# EEPROM-smt.net
KiCad netlist of a schematic drawn in EAGLE
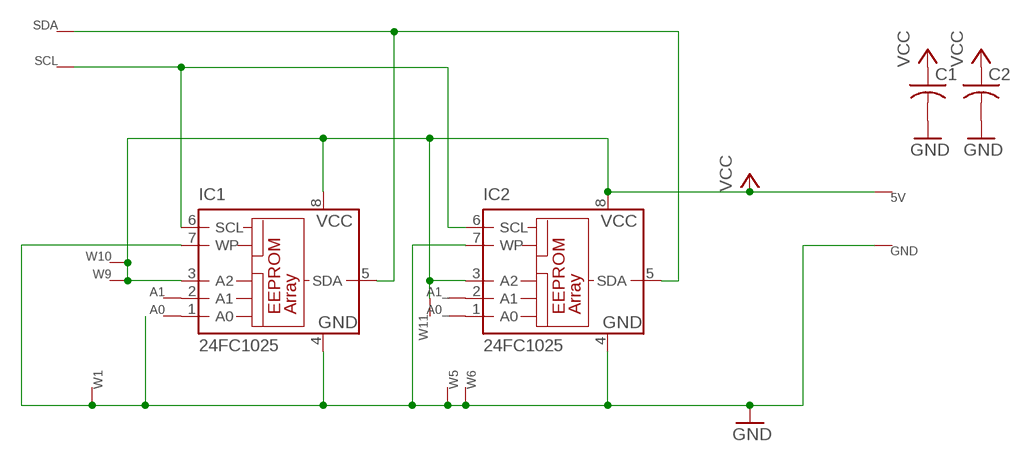
[diagram p0: schematic, sheet 1]

(export (version "E")
  (design (tool "Eeschema 10.0.6"))
  (components
    (comp (ref "5V")
      (value "WIRE-VIA8")
      (footprint "eagle-import:VIA8")
      (libsource (lib "eagle-import") (part "WIRE-VIA8"))
    )
    (comp (ref "A0")
      (value "WIRE-R6")
      (footprint "eagle-import:VIA6")
      (libsource (lib "eagle-import") (part "WIRE-R6"))
    )
    (comp (ref "A0_")
      (value "WIRE-R6")
      (footprint "eagle-import:VIA6")
      (libsource (lib "eagle-import") (part "WIRE-R6"))
    )
    (comp (ref "A1")
      (value "WIRE-R6")
      (footprint "eagle-import:VIA6")
      (libsource (lib "eagle-import") (part "WIRE-R6"))
    )
    (comp (ref "A1_")
      (value "WIRE-R6")
      (footprint "eagle-import:VIA6")
      (libsource (lib "eagle-import") (part "WIRE-R6"))
    )
    (comp (ref "C1")
      (value "C-USC0805")
      (footprint "eagle-import:C0805")
      (libsource (lib "eagle-import") (part "C-USC0805"))
    )
    (comp (ref "C2")
      (value "C-USC0805")
      (footprint "eagle-import:C0805")
      (libsource (lib "eagle-import") (part "C-USC0805"))
    )
    (comp (ref "GND")
      (value "WIRE-VIA8")
      (footprint "eagle-import:VIA8")
      (libsource (lib "eagle-import") (part "WIRE-VIA8"))
    )
    (comp (ref "IC1")
      (value "24FC1025")
      (footprint "eagle-import:SO-08")
      (fields (field (name "MF") "MICROCHIP") (field (name "MPN") "24LC128-I/SNG"))
      (libsource (lib "eagle-import") (part "24SNLC128"))
    )
    (comp (ref "IC2")
      (value "24FC1025")
      (footprint "eagle-import:SO-08")
      (fields (field (name "MF") "MICROCHIP") (field (name "MPN") "24LC128-I/SNG"))
      (libsource (lib "eagle-import") (part "24SNLC128"))
    )
    (comp (ref "SCL")
      (value "WIRE-VIA8")
      (footprint "eagle-import:VIA8")
      (libsource (lib "eagle-import") (part "WIRE-VIA8"))
    )
    (comp (ref "SDA")
      (value "WIRE-VIA8")
      (footprint "eagle-import:VIA8")
      (libsource (lib "eagle-import") (part "WIRE-VIA8"))
    )
    (comp (ref "W1")
      (value "WIRE-VIA8")
      (footprint "eagle-import:VIA8")
      (libsource (lib "eagle-import") (part "WIRE-VIA8"))
    )
    (comp (ref "W5")
      (value "WIRE-VIA8")
      (footprint "eagle-import:VIA8")
      (libsource (lib "eagle-import") (part "WIRE-VIA8"))
    )
    (comp (ref "W6")
      (value "WIRE-VIA8")
      (footprint "eagle-import:VIA8")
      (libsource (lib "eagle-import") (part "WIRE-VIA8"))
    )
    (comp (ref "W9")
      (value "WIRE-VIA8")
      (footprint "eagle-import:VIA8")
      (libsource (lib "eagle-import") (part "WIRE-VIA8"))
    )
    (comp (ref "W10")
      (value "WIRE-VIA8")
      (footprint "eagle-import:VIA8")
      (libsource (lib "eagle-import") (part "WIRE-VIA8"))
    )
    (comp (ref "W11")
      (value "WIRE-VIA8")
      (footprint "eagle-import:VIA8")
      (libsource (lib "eagle-import") (part "WIRE-VIA8"))
    )
  )
  (nets
    (net (code "1") (name "GND") (class "Default")
      (node (ref "C1") (pin "2") (pinfunction "2_2") (pintype "passive"))
      (node (ref "C2") (pin "2") (pinfunction "2_2") (pintype "passive"))
      (node (ref "GND") (pin "P$1") (pinfunction "P$1_P$1") (pintype "bidirectional"))
      (node (ref "IC1") (pin "4") (pinfunction "GND_4") (pintype "power_in"))
      (node (ref "IC1") (pin "7") (pinfunction "WP_7") (pintype "input"))
      (node (ref "IC2") (pin "4") (pinfunction "GND_4") (pintype "power_in"))
      (node (ref "IC2") (pin "7") (pinfunction "WP_7") (pintype "input"))
      (node (ref "W1") (pin "P$1") (pinfunction "P$1_P$1") (pintype "bidirectional"))
      (node (ref "W5") (pin "P$1") (pinfunction "P$1_P$1") (pintype "bidirectional"))
      (node (ref "W6") (pin "P$1") (pinfunction "P$1_P$1") (pintype "bidirectional"))
    )
    (net (code "2") (name "Net-(IC1-A0)") (class "Default")
      (node (ref "A0") (pin "P$1") (pinfunction "P$1_P$1") (pintype "bidirectional"))
      (node (ref "IC1") (pin "1") (pinfunction "A0_1") (pintype "input"))
    )
    (net (code "3") (name "Net-(IC1-A1)") (class "Default")
      (node (ref "A1") (pin "P$1") (pinfunction "P$1_P$1") (pintype "bidirectional"))
      (node (ref "IC1") (pin "2") (pinfunction "A1_2") (pintype "input"))
    )
    (net (code "4") (name "Net-(IC1-SCL)") (class "Default")
      (node (ref "IC1") (pin "6") (pinfunction "SCL_6") (pintype "input"))
      (node (ref "IC2") (pin "6") (pinfunction "SCL_6") (pintype "input"))
      (node (ref "SCL") (pin "P$1") (pinfunction "P$1_P$1") (pintype "bidirectional"))
    )
    (net (code "5") (name "Net-(IC1-SDA)") (class "Default")
      (node (ref "IC1") (pin "5") (pinfunction "SDA_5") (pintype "bidirectional"))
      (node (ref "IC2") (pin "5") (pinfunction "SDA_5") (pintype "bidirectional"))
      (node (ref "SDA") (pin "P$1") (pinfunction "P$1_P$1") (pintype "bidirectional"))
    )
    (net (code "6") (name "Net-(IC2-A0)") (class "Default")
      (node (ref "A0_") (pin "P$1") (pinfunction "P$1_P$1") (pintype "bidirectional"))
      (node (ref "IC2") (pin "1") (pinfunction "A0_1") (pintype "input"))
    )
    (net (code "7") (name "Net-(IC2-A1)") (class "Default")
      (node (ref "A1_") (pin "P$1") (pinfunction "P$1_P$1") (pintype "bidirectional"))
      (node (ref "IC2") (pin "2") (pinfunction "A1_2") (pintype "input"))
    )
    (net (code "8") (name "VCC") (class "Default")
      (node (ref "5V") (pin "P$1") (pinfunction "P$1_P$1") (pintype "bidirectional"))
      (node (ref "C1") (pin "1") (pinfunction "1_1") (pintype "passive"))
      (node (ref "C2") (pin "1") (pinfunction "1_1") (pintype "passive"))
      (node (ref "IC1") (pin "3") (pinfunction "A2_3") (pintype "input"))
      (node (ref "IC1") (pin "8") (pinfunction "VCC_8") (pintype "power_in"))
      (node (ref "IC2") (pin "3") (pinfunction "A2_3") (pintype "input"))
      (node (ref "IC2") (pin "8") (pinfunction "VCC_8") (pintype "power_in"))
      (node (ref "W10") (pin "P$1") (pinfunction "P$1_P$1") (pintype "bidirectional"))
      (node (ref "W11") (pin "P$1") (pinfunction "P$1_P$1") (pintype "bidirectional"))
      (node (ref "W9") (pin "P$1") (pinfunction "P$1_P$1") (pintype "bidirectional"))
    )
  )
)
